# main.net
KiCad netlist of a schematic drawn in EAGLE
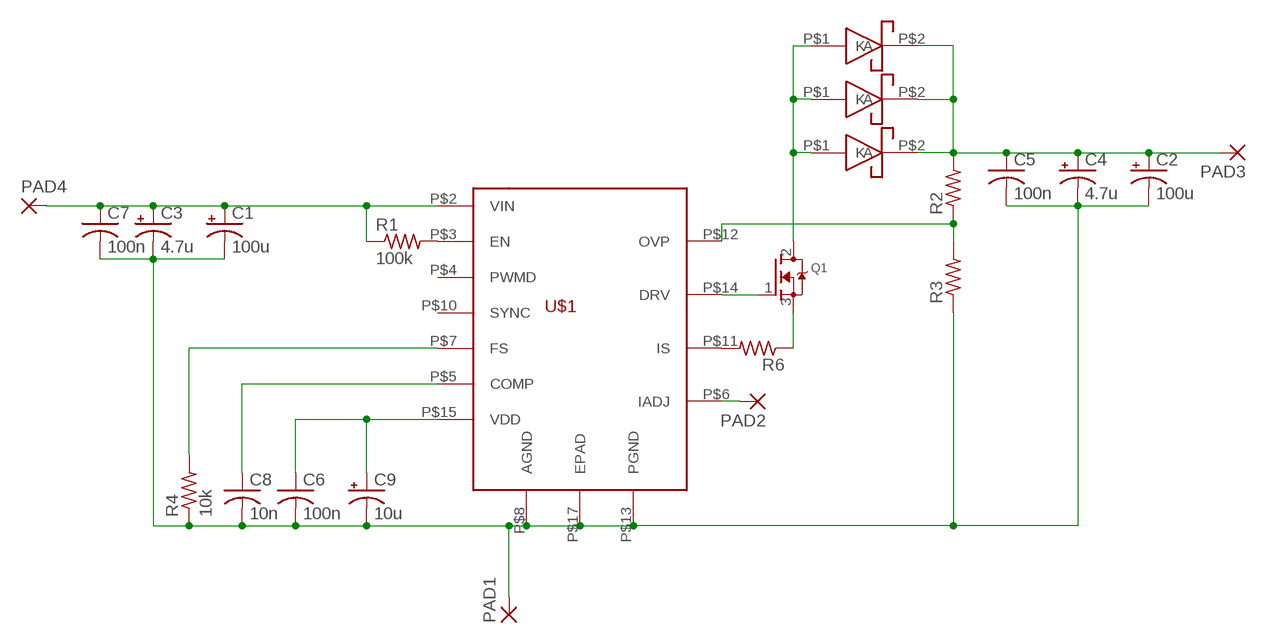
[diagram p0: schematic, sheet 1]

(export (version "E")
  (design (tool "Eeschema 10.0.6"))
  (components
    (comp (ref "C1")
      (value "100u")
      (footprint "eagle-import:E2-5")
      (libsource (lib "eagle-import") (part "CPOL-USE2-5"))
    )
    (comp (ref "C2")
      (value "100u")
      (footprint "eagle-import:E2-5")
      (libsource (lib "eagle-import") (part "CPOL-USE2-5"))
    )
    (comp (ref "C3")
      (value "4.7u")
      (footprint "eagle-import:E2-5")
      (libsource (lib "eagle-import") (part "CPOL-USE2-5"))
    )
    (comp (ref "C4")
      (value "4.7u")
      (footprint "eagle-import:E2-5")
      (libsource (lib "eagle-import") (part "CPOL-USE2-5"))
    )
    (comp (ref "C5")
      (value "100n")
      (footprint "eagle-import:C050-030X075")
      (libsource (lib "eagle-import") (part "C-US050-030X075"))
    )
    (comp (ref "C6")
      (value "100n")
      (footprint "eagle-import:C050-030X075")
      (libsource (lib "eagle-import") (part "C-US050-030X075"))
    )
    (comp (ref "C7")
      (value "100n")
      (footprint "eagle-import:C050-030X075")
      (libsource (lib "eagle-import") (part "C-US050-030X075"))
    )
    (comp (ref "C8")
      (value "10n")
      (footprint "eagle-import:C0603")
      (libsource (lib "eagle-import") (part "C-USC0603"))
    )
    (comp (ref "C9")
      (value "10u")
      (footprint "eagle-import:E2-5")
      (libsource (lib "eagle-import") (part "CPOL-USE2-5"))
    )
    (comp (ref "D1")
      (value "SS34")
      (footprint "eagle-import:DO-214AB")
      (libsource (lib "eagle-import") (part "SS34"))
    )
    (comp (ref "D2")
      (value "SS34")
      (footprint "eagle-import:DO-214AB")
      (libsource (lib "eagle-import") (part "SS34"))
    )
    (comp (ref "D3")
      (value "SS34")
      (footprint "eagle-import:DO-214AB")
      (libsource (lib "eagle-import") (part "SS34"))
    )
    (comp (ref "PAD1")
      (value "2,54/1,0")
      (footprint "eagle-import:2,54_1,0")
      (libsource (lib "eagle-import") (part "2,54/1,0"))
    )
    (comp (ref "PAD2")
      (value "2,54/1,0")
      (footprint "eagle-import:2,54_1,0")
      (libsource (lib "eagle-import") (part "2,54/1,0"))
    )
    (comp (ref "PAD3")
      (value "2,54/1,0")
      (footprint "eagle-import:2,54_1,0")
      (libsource (lib "eagle-import") (part "2,54/1,0"))
    )
    (comp (ref "PAD4")
      (value "2,54/1,0")
      (footprint "eagle-import:2,54_1,0")
      (libsource (lib "eagle-import") (part "2,54/1,0"))
    )
    (comp (ref "Q1")
      (value "MOSFET-NGDS_TO220V")
      (footprint "eagle-import:TO220V")
      (libsource (lib "eagle-import") (part "MOSFET-NGDS_TO220V"))
    )
    (comp (ref "R1")
      (value "100k")
      (footprint "eagle-import:R0603")
      (libsource (lib "eagle-import") (part "R-US_R0603"))
    )
    (comp (ref "R2")
      (value "R-US_R0603")
      (footprint "eagle-import:R0603")
      (libsource (lib "eagle-import") (part "R-US_R0603"))
    )
    (comp (ref "R3")
      (value "R-US_R0603")
      (footprint "eagle-import:R0603")
      (libsource (lib "eagle-import") (part "R-US_R0603"))
    )
    (comp (ref "R4")
      (value "10k")
      (footprint "eagle-import:R0603")
      (libsource (lib "eagle-import") (part "R-US_R0603"))
    )
    (comp (ref "R6")
      (value "R-US_R0603")
      (footprint "eagle-import:R0603")
      (libsource (lib "eagle-import") (part "R-US_R0603"))
    )
    (comp (ref "U$1")
      (value "MIC3232")
      (footprint "eagle-import:TSSOP16_EPAD")
      (libsource (lib "eagle-import") (part "MIC3232"))
    )
  )
  (nets
    (net (code "1") (name "Net-(D1-A)") (class "Default")
      (node (ref "D1") (pin "P$1") (pinfunction "A_P$1") (pintype "bidirectional"))
      (node (ref "D2") (pin "P$1") (pinfunction "A_P$1") (pintype "bidirectional"))
      (node (ref "D3") (pin "P$1") (pinfunction "A_P$1") (pintype "bidirectional"))
      (node (ref "Q1") (pin "2") (pinfunction "D_2") (pintype "bidirectional"))
    )
    (net (code "2") (name "Net-(D1-K)") (class "Default")
      (node (ref "C2") (pin "+") (pinfunction "+_+") (pintype "passive"))
      (node (ref "C4") (pin "+") (pinfunction "+_+") (pintype "passive"))
      (node (ref "C5") (pin "1") (pinfunction "1_1") (pintype "passive"))
      (node (ref "D1") (pin "P$2") (pinfunction "K_P$2") (pintype "bidirectional"))
      (node (ref "D2") (pin "P$2") (pinfunction "K_P$2") (pintype "bidirectional"))
      (node (ref "D3") (pin "P$2") (pinfunction "K_P$2") (pintype "bidirectional"))
      (node (ref "PAD3") (pin "1") (pinfunction "P_1") (pintype "passive"))
      (node (ref "R2") (pin "2") (pinfunction "2_2") (pintype "passive"))
    )
    (net (code "3") (name "Net-(PAD1-P)") (class "Default")
      (node (ref "C1") (pin "-") (pinfunction "-_-") (pintype "passive"))
      (node (ref "C2") (pin "-") (pinfunction "-_-") (pintype "passive"))
      (node (ref "C3") (pin "-") (pinfunction "-_-") (pintype "passive"))
      (node (ref "C4") (pin "-") (pinfunction "-_-") (pintype "passive"))
      (node (ref "C5") (pin "2") (pinfunction "2_2") (pintype "passive"))
      (node (ref "C6") (pin "2") (pinfunction "2_2") (pintype "passive"))
      (node (ref "C7") (pin "2") (pinfunction "2_2") (pintype "passive"))
      (node (ref "C8") (pin "2") (pinfunction "2_2") (pintype "passive"))
      (node (ref "C9") (pin "-") (pinfunction "-_-") (pintype "passive"))
      (node (ref "PAD1") (pin "1") (pinfunction "P_1") (pintype "passive"))
      (node (ref "R3") (pin "1") (pinfunction "1_1") (pintype "passive"))
      (node (ref "R4") (pin "1") (pinfunction "1_1") (pintype "passive"))
      (node (ref "U$1") (pin "P$13") (pinfunction "PGND_P$13") (pintype "bidirectional"))
      (node (ref "U$1") (pin "P$17") (pinfunction "EPAD_P$17") (pintype "bidirectional"))
      (node (ref "U$1") (pin "P$8") (pinfunction "AGND_P$8") (pintype "bidirectional"))
    )
    (net (code "4") (name "Net-(PAD2-P)") (class "Default")
      (node (ref "PAD2") (pin "1") (pinfunction "P_1") (pintype "passive"))
      (node (ref "U$1") (pin "P$6") (pinfunction "IADJ_P$6") (pintype "bidirectional"))
    )
    (net (code "5") (name "Net-(PAD4-P)") (class "Default")
      (node (ref "C1") (pin "+") (pinfunction "+_+") (pintype "passive"))
      (node (ref "C3") (pin "+") (pinfunction "+_+") (pintype "passive"))
      (node (ref "C7") (pin "1") (pinfunction "1_1") (pintype "passive"))
      (node (ref "PAD4") (pin "1") (pinfunction "P_1") (pintype "passive"))
      (node (ref "R1") (pin "1") (pinfunction "1_1") (pintype "passive"))
      (node (ref "U$1") (pin "P$2") (pinfunction "VIN_P$2") (pintype "bidirectional"))
    )
    (net (code "6") (name "Net-(Q1-G)") (class "Default")
      (node (ref "Q1") (pin "1") (pinfunction "G_1") (pintype "bidirectional"))
      (node (ref "U$1") (pin "P$14") (pinfunction "DRV_P$14") (pintype "bidirectional"))
    )
    (net (code "7") (name "Net-(Q1-S)") (class "Default")
      (node (ref "Q1") (pin "3") (pinfunction "S_3") (pintype "bidirectional"))
      (node (ref "R6") (pin "1") (pinfunction "1_1") (pintype "passive"))
    )
    (net (code "8") (name "Net-(U$1-COMP)") (class "Default")
      (node (ref "C8") (pin "1") (pinfunction "1_1") (pintype "passive"))
      (node (ref "U$1") (pin "P$5") (pinfunction "COMP_P$5") (pintype "bidirectional"))
    )
    (net (code "9") (name "Net-(U$1-EN)") (class "Default")
      (node (ref "R1") (pin "2") (pinfunction "2_2") (pintype "passive"))
      (node (ref "U$1") (pin "P$3") (pinfunction "EN_P$3") (pintype "bidirectional"))
    )
    (net (code "10") (name "Net-(U$1-FS)") (class "Default")
      (node (ref "R4") (pin "2") (pinfunction "2_2") (pintype "passive"))
      (node (ref "U$1") (pin "P$7") (pinfunction "FS_P$7") (pintype "bidirectional"))
    )
    (net (code "11") (name "Net-(U$1-IS)") (class "Default")
      (node (ref "R6") (pin "2") (pinfunction "2_2") (pintype "passive"))
      (node (ref "U$1") (pin "P$11") (pinfunction "IS_P$11") (pintype "bidirectional"))
    )
    (net (code "12") (name "Net-(U$1-OVP)") (class "Default")
      (node (ref "R2") (pin "1") (pinfunction "1_1") (pintype "passive"))
      (node (ref "R3") (pin "2") (pinfunction "2_2") (pintype "passive"))
      (node (ref "U$1") (pin "P$12") (pinfunction "OVP_P$12") (pintype "bidirectional"))
    )
    (net (code "13") (name "Net-(U$1-VDD)") (class "Default")
      (node (ref "C6") (pin "1") (pinfunction "1_1") (pintype "passive"))
      (node (ref "C9") (pin "+") (pinfunction "+_+") (pintype "passive"))
      (node (ref "U$1") (pin "P$15") (pinfunction "VDD_P$15") (pintype "bidirectional"))
    )
    (net (code "14") (name "unconnected-(U$1-PWMD-PadP$4)") (class "Default")
      (node (ref "U$1") (pin "P$4") (pinfunction "PWMD_P$4") (pintype "bidirectional"))
    )
    (net (code "15") (name "unconnected-(U$1-SYNC-PadP$10)") (class "Default")
      (node (ref "U$1") (pin "P$10") (pinfunction "SYNC_P$10") (pintype "bidirectional"))
    )
  )
)
